# RelayDelay.net
KiCad netlist of a schematic drawn in EAGLE
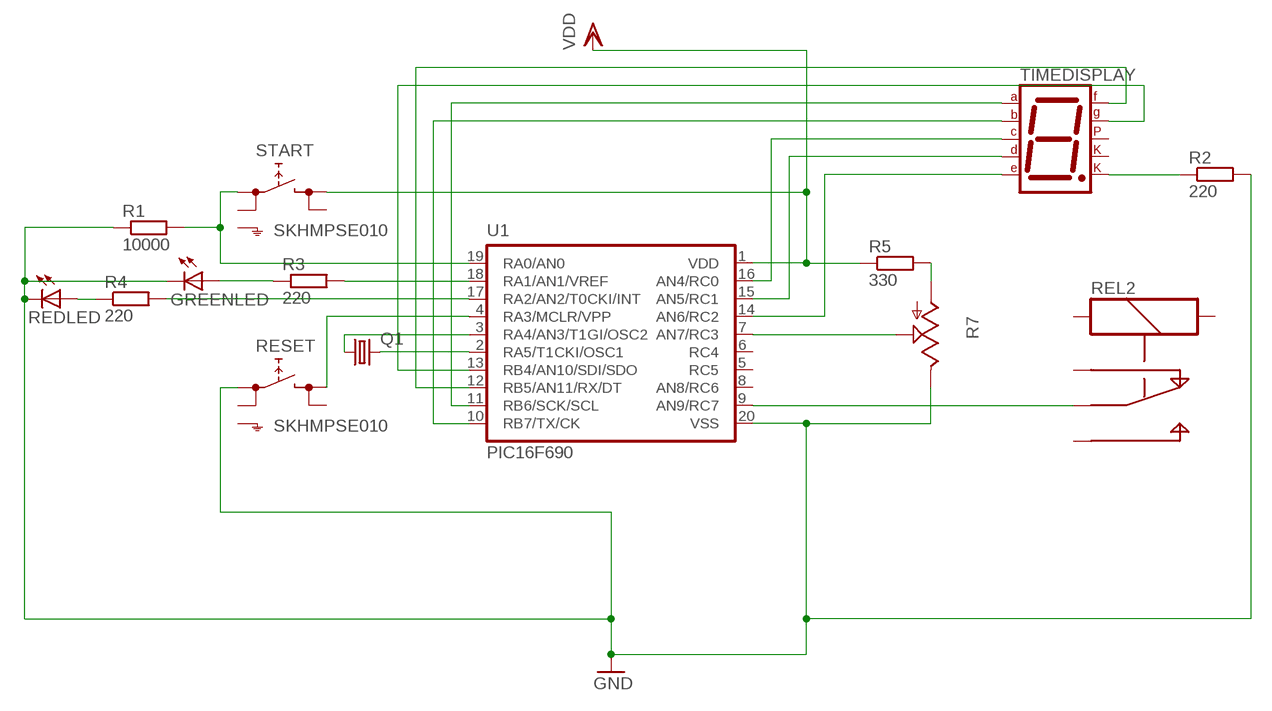
[diagram p0: schematic, sheet 1]

(export (version "E")
  (design (tool "Eeschema 10.0.6"))
  (components
    (comp (ref "GREENLED")
      (value "LED")
      (footprint "eagle-import:SMARTLED-TTW")
      (libsource (lib "eagle-import") (part "LED"))
    )
    (comp (ref "Q1")
      (value "CRYSTALHC49S")
      (footprint "eagle-import:HC49_S")
      (libsource (lib "eagle-import") (part "CRYSTALHC49S"))
    )
    (comp (ref "R1")
      (value "10000")
      (footprint "eagle-import:0204_5")
      (libsource (lib "eagle-import") (part "resistor_R-EU_0204/5"))
    )
    (comp (ref "R2")
      (value "220")
      (footprint "eagle-import:0204_5")
      (libsource (lib "eagle-import") (part "resistor_R-EU_0204/5"))
    )
    (comp (ref "R3")
      (value "220")
      (footprint "eagle-import:0204_5")
      (libsource (lib "eagle-import") (part "R-EU_0204/5"))
    )
    (comp (ref "R4")
      (value "220")
      (footprint "eagle-import:0204_5")
      (libsource (lib "eagle-import") (part "R-EU_0204/5"))
    )
    (comp (ref "R5")
      (value "330")
      (footprint "eagle-import:0204_5")
      (libsource (lib "eagle-import") (part "resistor_R-EU_0204/5"))
    )
    (comp (ref "R7")
      (value "TRIM_US-CIP20C-6MM")
      (footprint "eagle-import:CIP20C-6MM")
      (libsource (lib "eagle-import") (part "TRIM_US-CIP20C-6MM"))
    )
    (comp (ref "REDLED")
      (value "LED")
      (footprint "eagle-import:SMARTLED-TTW")
      (libsource (lib "eagle-import") (part "LED"))
    )
    (comp (ref "REL2")
      (value "REL-5PIN")
      (footprint "eagle-import:REL-5PIN")
      (libsource (lib "eagle-import") (part "REL-5PIN"))
    )
    (comp (ref "RESET")
      (value "SKHMPSE010")
      (footprint "eagle-import:SKHMPXE010")
      (libsource (lib "eagle-import") (part "SKHMPE010S"))
    )
    (comp (ref "START")
      (value "SKHMPSE010")
      (footprint "eagle-import:SKHMPXE010")
      (libsource (lib "eagle-import") (part "SKHMPE010S"))
    )
    (comp (ref "TIMEDISPLAY")
      (value "7SEG-CK")
      (footprint "eagle-import:7SEG-13")
      (libsource (lib "eagle-import") (part "7SEG-CK"))
    )
    (comp (ref "U1")
      (value "PIC16F690")
      (footprint "eagle-import:DIL20")
      (libsource (lib "eagle-import") (part "PIC16F6XX"))
    )
  )
  (nets
    (net (code "1") (name "GND") (class "Default")
      (node (ref "GREENLED") (pin "C@1") (pinfunction "C_C@1") (pintype "passive"))
      (node (ref "R1") (pin "1") (pinfunction "1_1") (pintype "passive"))
      (node (ref "R2") (pin "2") (pinfunction "2_2") (pintype "passive"))
      (node (ref "R7") (pin "E") (pinfunction "E_E") (pintype "passive"))
      (node (ref "REDLED") (pin "C@1") (pinfunction "C_C@1") (pintype "passive"))
      (node (ref "RESET") (pin "1") (pinfunction "1.1_1") (pintype "passive"))
      (node (ref "U1") (pin "20") (pinfunction "VSS_20") (pintype "power_in"))
    )
    (net (code "2") (name "Net-(GREENLED-A)") (class "Default")
      (node (ref "GREENLED") (pin "A@1") (pinfunction "A_A@1") (pintype "passive"))
      (node (ref "R3") (pin "1") (pinfunction "1_1") (pintype "passive"))
    )
    (net (code "3") (name "Net-(R5-Pad2)") (class "Default")
      (node (ref "R5") (pin "2") (pinfunction "2_2") (pintype "passive"))
      (node (ref "R7") (pin "A") (pinfunction "A_A") (pintype "passive"))
    )
    (net (code "4") (name "Net-(REDLED-A)") (class "Default")
      (node (ref "R4") (pin "1") (pinfunction "1_1") (pintype "passive"))
      (node (ref "REDLED") (pin "A@1") (pinfunction "A_A@1") (pintype "passive"))
    )
    (net (code "5") (name "Net-(RESET-2.1)") (class "Default")
      (node (ref "RESET") (pin "3") (pinfunction "2.1_3") (pintype "passive"))
      (node (ref "U1") (pin "4") (pinfunction "RA3/MCLR/VPP_4") (pintype "input"))
    )
    (net (code "6") (name "Net-(START-1.1)") (class "Default")
      (node (ref "R1") (pin "2") (pinfunction "2_2") (pintype "passive"))
      (node (ref "START") (pin "1") (pinfunction "1.1_1") (pintype "passive"))
      (node (ref "U1") (pin "19") (pinfunction "RA0/AN0_19") (pintype "bidirectional"))
    )
    (net (code "7") (name "Net-(TIMEDISPLAY-A)") (class "Default")
      (node (ref "TIMEDISPLAY") (pin "7") (pinfunction "A_7") (pintype "passive"))
      (node (ref "U1") (pin "11") (pinfunction "RB6/SCK/SCL_11") (pintype "bidirectional"))
    )
    (net (code "8") (name "Net-(TIMEDISPLAY-B)") (class "Default")
      (node (ref "TIMEDISPLAY") (pin "6") (pinfunction "B_6") (pintype "passive"))
      (node (ref "U1") (pin "10") (pinfunction "RB7/TX/CK_10") (pintype "bidirectional"))
    )
    (net (code "9") (name "Net-(TIMEDISPLAY-C)") (class "Default")
      (node (ref "TIMEDISPLAY") (pin "4") (pinfunction "C_4") (pintype "passive"))
      (node (ref "U1") (pin "16") (pinfunction "AN4/RC0_16") (pintype "bidirectional"))
    )
    (net (code "10") (name "Net-(TIMEDISPLAY-CK2)") (class "Default")
      (node (ref "R2") (pin "1") (pinfunction "1_1") (pintype "passive"))
      (node (ref "TIMEDISPLAY") (pin "8") (pinfunction "CK2_8") (pintype "passive"))
    )
    (net (code "11") (name "Net-(TIMEDISPLAY-D)") (class "Default")
      (node (ref "TIMEDISPLAY") (pin "2") (pinfunction "D_2") (pintype "passive"))
      (node (ref "U1") (pin "15") (pinfunction "AN5/RC1_15") (pintype "bidirectional"))
    )
    (net (code "12") (name "Net-(TIMEDISPLAY-E)") (class "Default")
      (node (ref "TIMEDISPLAY") (pin "1") (pinfunction "E_1") (pintype "passive"))
      (node (ref "U1") (pin "14") (pinfunction "AN6/RC2_14") (pintype "bidirectional"))
    )
    (net (code "13") (name "Net-(TIMEDISPLAY-F)") (class "Default")
      (node (ref "TIMEDISPLAY") (pin "9") (pinfunction "F_9") (pintype "passive"))
      (node (ref "U1") (pin "12") (pinfunction "RB5/AN11/RX/DT_12") (pintype "bidirectional"))
    )
    (net (code "14") (name "Net-(TIMEDISPLAY-G)") (class "Default")
      (node (ref "TIMEDISPLAY") (pin "10") (pinfunction "G_10") (pintype "passive"))
      (node (ref "U1") (pin "13") (pinfunction "RB4/AN10/SDI/SDO_13") (pintype "bidirectional"))
    )
    (net (code "15") (name "Net-(U1-AN7{slash}RC3)") (class "Default")
      (node (ref "R7") (pin "S") (pinfunction "S_S") (pintype "passive"))
      (node (ref "U1") (pin "7") (pinfunction "AN7/RC3_7") (pintype "bidirectional"))
    )
    (net (code "16") (name "Net-(U1-AN9{slash}RC7)") (class "Default")
      (node (ref "REL2") (pin "C") (pinfunction "C_C") (pintype "passive"))
      (node (ref "U1") (pin "9") (pinfunction "AN9/RC7_9") (pintype "bidirectional"))
    )
    (net (code "17") (name "Net-(U1-RA1{slash}AN1{slash}VREF)") (class "Default")
      (node (ref "R3") (pin "2") (pinfunction "2_2") (pintype "passive"))
      (node (ref "U1") (pin "18") (pinfunction "RA1/AN1/VREF_18") (pintype "bidirectional"))
    )
    (net (code "18") (name "Net-(U1-RA2{slash}AN2{slash}T0CKI{slash}INT)") (class "Default")
      (node (ref "R4") (pin "2") (pinfunction "2_2") (pintype "passive"))
      (node (ref "U1") (pin "17") (pinfunction "RA2/AN2/T0CKI/INT_17") (pintype "bidirectional"))
    )
    (net (code "19") (name "Net-(U1-RA4{slash}AN3{slash}T1GI{slash}OSC2)") (class "Default")
      (node (ref "Q1") (pin "1") (pinfunction "1_1") (pintype "passive"))
      (node (ref "U1") (pin "3") (pinfunction "RA4/AN3/T1GI/OSC2_3") (pintype "bidirectional"))
    )
    (net (code "20") (name "Net-(U1-RA5{slash}T1CKI{slash}OSC1)") (class "Default")
      (node (ref "Q1") (pin "2") (pinfunction "2_2") (pintype "passive"))
      (node (ref "U1") (pin "2") (pinfunction "RA5/T1CKI/OSC1_2") (pintype "bidirectional"))
    )
    (net (code "21") (name "VDD") (class "Default")
      (node (ref "R5") (pin "1") (pinfunction "1_1") (pintype "passive"))
      (node (ref "START") (pin "3") (pinfunction "2.1_3") (pintype "passive"))
      (node (ref "U1") (pin "1") (pinfunction "VDD_1") (pintype "power_in"))
    )
    (net (code "22") (name "unconnected-(REL2-PadO)") (class "Default")
      (node (ref "REL2") (pin "O") (pinfunction "O_O") (pintype "passive"))
    )
    (net (code "23") (name "unconnected-(REL2-PadS)") (class "Default")
      (node (ref "REL2") (pin "S") (pinfunction "S_S") (pintype "passive"))
    )
    (net (code "24") (name "unconnected-(REL2-PadS1)") (class "Default")
      (node (ref "REL2") (pin "S1") (pinfunction "S1_S1") (pintype "passive"))
    )
    (net (code "25") (name "unconnected-(REL2-PadS2)") (class "Default")
      (node (ref "REL2") (pin "S2") (pinfunction "S2_S2") (pintype "passive"))
    )
    (net (code "26") (name "unconnected-(RESET-1.2-Pad2)") (class "Default")
      (node (ref "RESET") (pin "2") (pinfunction "1.2_2") (pintype "passive"))
    )
    (net (code "27") (name "unconnected-(RESET-2.2-Pad4)") (class "Default")
      (node (ref "RESET") (pin "4") (pinfunction "2.2_4") (pintype "passive"))
    )
    (net (code "28") (name "unconnected-(RESET-SH-Pad5)") (class "Default")
      (node (ref "RESET") (pin "5") (pinfunction "SH_5") (pintype "passive"))
    )
    (net (code "29") (name "unconnected-(START-1.2-Pad2)") (class "Default")
      (node (ref "START") (pin "2") (pinfunction "1.2_2") (pintype "passive"))
    )
    (net (code "30") (name "unconnected-(START-2.2-Pad4)") (class "Default")
      (node (ref "START") (pin "4") (pinfunction "2.2_4") (pintype "passive"))
    )
    (net (code "31") (name "unconnected-(START-SH-Pad5)") (class "Default")
      (node (ref "START") (pin "5") (pinfunction "SH_5") (pintype "passive"))
    )
    (net (code "32") (name "unconnected-(TIMEDISPLAY-CK1-Pad3)") (class "Default")
      (node (ref "TIMEDISPLAY") (pin "3") (pinfunction "CK1_3") (pintype "passive"))
    )
    (net (code "33") (name "unconnected-(TIMEDISPLAY-DP-Pad5)") (class "Default")
      (node (ref "TIMEDISPLAY") (pin "5") (pinfunction "DP_5") (pintype "passive"))
    )
    (net (code "34") (name "unconnected-(U1-AN8{slash}RC6-Pad8)") (class "Default")
      (node (ref "U1") (pin "8") (pinfunction "AN8/RC6_8") (pintype "bidirectional"))
    )
    (net (code "35") (name "unconnected-(U1-RC4-Pad6)") (class "Default")
      (node (ref "U1") (pin "6") (pinfunction "RC4_6") (pintype "bidirectional"))
    )
    (net (code "36") (name "unconnected-(U1-RC5-Pad5)") (class "Default")
      (node (ref "U1") (pin "5") (pinfunction "RC5_5") (pintype "bidirectional"))
    )
  )
)
